# cs4272_test.net
KiCad netlist of a schematic drawn in EAGLE
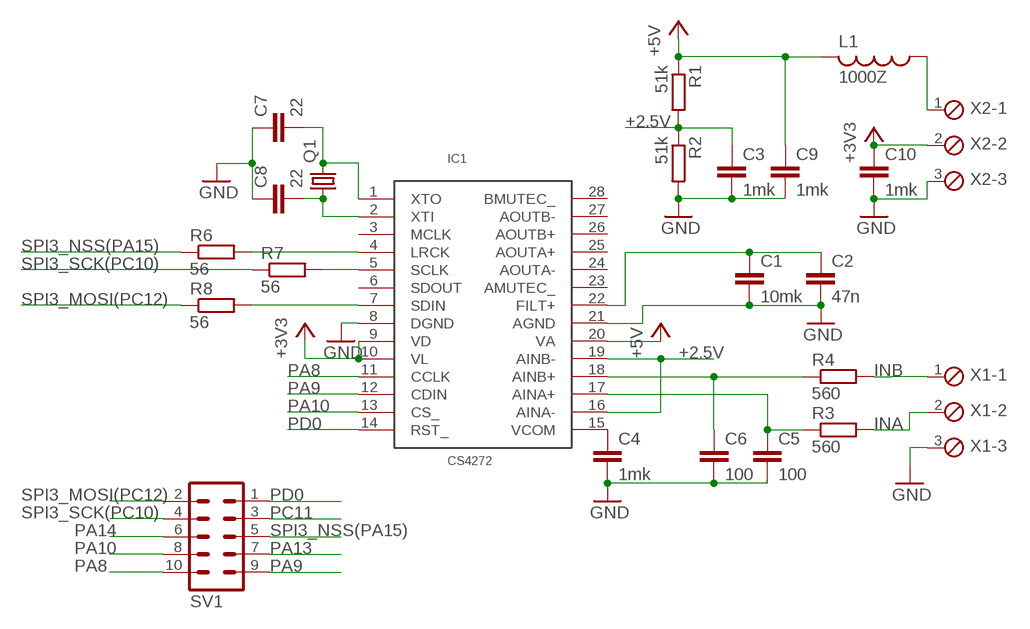
[diagram p0: schematic, sheet 1]

(export (version "E")
  (design (tool "Eeschema 10.0.6"))
  (components
    (comp (ref "C1")
      (value "10mk")
      (footprint "eagle-import:C0805")
      (libsource (lib "eagle-import") (part "C-EUC0805"))
    )
    (comp (ref "C2")
      (value "47n")
      (footprint "eagle-import:C0805")
      (libsource (lib "eagle-import") (part "C-EUC0805"))
    )
    (comp (ref "C3")
      (value "1mk")
      (footprint "eagle-import:C0603")
      (libsource (lib "eagle-import") (part "C-EUC0603"))
    )
    (comp (ref "C4")
      (value "1mk")
      (footprint "eagle-import:C0603")
      (libsource (lib "eagle-import") (part "C-EUC0603"))
    )
    (comp (ref "C5")
      (value "100")
      (footprint "eagle-import:C0805")
      (libsource (lib "eagle-import") (part "C-EUC0805"))
    )
    (comp (ref "C6")
      (value "100")
      (footprint "eagle-import:C0805")
      (libsource (lib "eagle-import") (part "C-EUC0805"))
    )
    (comp (ref "C7")
      (value "22")
      (footprint "eagle-import:C0603")
      (libsource (lib "eagle-import") (part "C-EUC0603"))
    )
    (comp (ref "C8")
      (value "22")
      (footprint "eagle-import:C0603")
      (libsource (lib "eagle-import") (part "C-EUC0603"))
    )
    (comp (ref "C9")
      (value "1mk")
      (footprint "eagle-import:C0603")
      (libsource (lib "eagle-import") (part "C-EUC0603"))
    )
    (comp (ref "C10")
      (value "1mk")
      (footprint "eagle-import:C0603")
      (libsource (lib "eagle-import") (part "C-EUC0603"))
    )
    (comp (ref "IC1")
      (value "CS4272")
      (footprint "eagle-import:TSSOP28")
      (libsource (lib "eagle-import") (part "CS4272"))
    )
    (comp (ref "L1")
      (value "1000Z")
      (footprint "eagle-import:C0805")
      (libsource (lib "eagle-import") (part "L-USL0805"))
    )
    (comp (ref "Q1")
      (value "CRYSTALHC49S")
      (footprint "eagle-import:HC49_S")
      (libsource (lib "eagle-import") (part "CRYSTALHC49S"))
    )
    (comp (ref "R1")
      (value "51k")
      (footprint "eagle-import:R0603")
      (libsource (lib "eagle-import") (part "R-EU_R0603"))
    )
    (comp (ref "R2")
      (value "51k")
      (footprint "eagle-import:R0603")
      (libsource (lib "eagle-import") (part "R-EU_R0603"))
    )
    (comp (ref "R3")
      (value "560")
      (footprint "eagle-import:R0603")
      (libsource (lib "eagle-import") (part "R-EU_R0603"))
    )
    (comp (ref "R4")
      (value "560")
      (footprint "eagle-import:R0603")
      (libsource (lib "eagle-import") (part "R-EU_R0603"))
    )
    (comp (ref "R6")
      (value "56")
      (footprint "eagle-import:R0603")
      (libsource (lib "eagle-import") (part "R-EU_R0603"))
    )
    (comp (ref "R7")
      (value "56")
      (footprint "eagle-import:R0603")
      (libsource (lib "eagle-import") (part "R-EU_R0603"))
    )
    (comp (ref "R8")
      (value "56")
      (footprint "eagle-import:R0603")
      (libsource (lib "eagle-import") (part "R-EU_R0603"))
    )
    (comp (ref "SV1")
      (value "ML10")
      (footprint "eagle-import:ML10")
      (libsource (lib "eagle-import") (part "ML10"))
    )
    (comp (ref "X1")
      (value "MPT3")
      (footprint "eagle-import:3POL254")
      (libsource (lib "eagle-import") (part "MPT3"))
    )
    (comp (ref "X2")
      (value "MPT3")
      (footprint "eagle-import:3POL254")
      (libsource (lib "eagle-import") (part "MPT3"))
    )
  )
  (nets
    (net (code "1") (name "+3V3") (class "Default")
      (node (ref "C10") (pin "1") (pinfunction "1_1") (pintype "passive"))
      (node (ref "IC1") (pin "10") (pinfunction "VL_10") (pintype "bidirectional"))
      (node (ref "IC1") (pin "9") (pinfunction "VD_9") (pintype "bidirectional"))
      (node (ref "X2") (pin "2") (pinfunction "1_2") (pintype "passive"))
    )
    (net (code "2") (name "+5V") (class "Default")
      (node (ref "C9") (pin "1") (pinfunction "1_1") (pintype "passive"))
      (node (ref "IC1") (pin "20") (pinfunction "VA_20") (pintype "bidirectional"))
      (node (ref "L1") (pin "2") (pinfunction "2_2") (pintype "passive"))
      (node (ref "R1") (pin "1") (pinfunction "1_1") (pintype "passive"))
    )
    (net (code "3") (name "/+2.5V") (class "Default")
      (node (ref "C3") (pin "1") (pinfunction "1_1") (pintype "passive"))
      (node (ref "IC1") (pin "16") (pinfunction "AINA-_16") (pintype "bidirectional"))
      (node (ref "IC1") (pin "19") (pinfunction "AINB-_19") (pintype "bidirectional"))
      (node (ref "R1") (pin "2") (pinfunction "2_2") (pintype "passive"))
      (node (ref "R2") (pin "1") (pinfunction "1_1") (pintype "passive"))
    )
    (net (code "4") (name "/INA") (class "Default")
      (node (ref "R3") (pin "2") (pinfunction "2_2") (pintype "passive"))
      (node (ref "X1") (pin "2") (pinfunction "1_2") (pintype "passive"))
    )
    (net (code "5") (name "/INB") (class "Default")
      (node (ref "R4") (pin "2") (pinfunction "2_2") (pintype "passive"))
      (node (ref "X1") (pin "1") (pinfunction "1_1") (pintype "passive"))
    )
    (net (code "6") (name "/PA8") (class "Default")
      (node (ref "IC1") (pin "11") (pinfunction "CCLK_11") (pintype "bidirectional"))
      (node (ref "SV1") (pin "10") (pinfunction "10_10") (pintype "passive"))
    )
    (net (code "7") (name "/PA9") (class "Default")
      (node (ref "IC1") (pin "12") (pinfunction "CDIN_12") (pintype "bidirectional"))
      (node (ref "SV1") (pin "9") (pinfunction "9_9") (pintype "passive"))
    )
    (net (code "8") (name "/PA10") (class "Default")
      (node (ref "IC1") (pin "13") (pinfunction "CS__13") (pintype "bidirectional"))
      (node (ref "SV1") (pin "8") (pinfunction "8_8") (pintype "passive"))
    )
    (net (code "9") (name "/PA13") (class "Default")
      (node (ref "SV1") (pin "7") (pinfunction "7_7") (pintype "passive"))
    )
    (net (code "10") (name "/PA14") (class "Default")
      (node (ref "SV1") (pin "6") (pinfunction "6_6") (pintype "passive"))
    )
    (net (code "11") (name "/PC11") (class "Default")
      (node (ref "SV1") (pin "3") (pinfunction "3_3") (pintype "passive"))
    )
    (net (code "12") (name "/PD0") (class "Default")
      (node (ref "IC1") (pin "14") (pinfunction "RST__14") (pintype "bidirectional"))
      (node (ref "SV1") (pin "1") (pinfunction "1_1") (pintype "passive"))
    )
    (net (code "13") (name "/SPI3_MOSI(PC12)") (class "Default")
      (node (ref "R8") (pin "1") (pinfunction "1_1") (pintype "passive"))
      (node (ref "SV1") (pin "2") (pinfunction "2_2") (pintype "passive"))
    )
    (net (code "14") (name "/SPI3_NSS(PA15)") (class "Default")
      (node (ref "R6") (pin "1") (pinfunction "1_1") (pintype "passive"))
      (node (ref "SV1") (pin "5") (pinfunction "5_5") (pintype "passive"))
    )
    (net (code "15") (name "/SPI3_SCK(PC10)") (class "Default")
      (node (ref "R7") (pin "1") (pinfunction "1_1") (pintype "passive"))
      (node (ref "SV1") (pin "4") (pinfunction "4_4") (pintype "passive"))
    )
    (net (code "16") (name "GND") (class "Default")
      (node (ref "C1") (pin "2") (pinfunction "2_2") (pintype "passive"))
      (node (ref "C10") (pin "2") (pinfunction "2_2") (pintype "passive"))
      (node (ref "C2") (pin "2") (pinfunction "2_2") (pintype "passive"))
      (node (ref "C3") (pin "2") (pinfunction "2_2") (pintype "passive"))
      (node (ref "C4") (pin "2") (pinfunction "2_2") (pintype "passive"))
      (node (ref "C5") (pin "2") (pinfunction "2_2") (pintype "passive"))
      (node (ref "C6") (pin "2") (pinfunction "2_2") (pintype "passive"))
      (node (ref "C7") (pin "1") (pinfunction "1_1") (pintype "passive"))
      (node (ref "C8") (pin "1") (pinfunction "1_1") (pintype "passive"))
      (node (ref "C9") (pin "2") (pinfunction "2_2") (pintype "passive"))
      (node (ref "IC1") (pin "21") (pinfunction "AGND_21") (pintype "bidirectional"))
      (node (ref "IC1") (pin "8") (pinfunction "DGND_8") (pintype "bidirectional"))
      (node (ref "R2") (pin "2") (pinfunction "2_2") (pintype "passive"))
      (node (ref "X1") (pin "3") (pinfunction "1_3") (pintype "passive"))
      (node (ref "X2") (pin "3") (pinfunction "1_3") (pintype "passive"))
    )
    (net (code "17") (name "Net-(IC1-AINA+)") (class "Default")
      (node (ref "C5") (pin "1") (pinfunction "1_1") (pintype "passive"))
      (node (ref "IC1") (pin "17") (pinfunction "AINA+_17") (pintype "bidirectional"))
      (node (ref "R3") (pin "1") (pinfunction "1_1") (pintype "passive"))
    )
    (net (code "18") (name "Net-(IC1-AINB+)") (class "Default")
      (node (ref "C6") (pin "1") (pinfunction "1_1") (pintype "passive"))
      (node (ref "IC1") (pin "18") (pinfunction "AINB+_18") (pintype "bidirectional"))
      (node (ref "R4") (pin "1") (pinfunction "1_1") (pintype "passive"))
    )
    (net (code "19") (name "Net-(IC1-FILT+)") (class "Default")
      (node (ref "C1") (pin "1") (pinfunction "1_1") (pintype "passive"))
      (node (ref "C2") (pin "1") (pinfunction "1_1") (pintype "passive"))
      (node (ref "IC1") (pin "22") (pinfunction "FILT+_22") (pintype "bidirectional"))
    )
    (net (code "20") (name "Net-(IC1-LRCK)") (class "Default")
      (node (ref "IC1") (pin "4") (pinfunction "LRCK_4") (pintype "bidirectional"))
      (node (ref "R6") (pin "2") (pinfunction "2_2") (pintype "passive"))
    )
    (net (code "21") (name "Net-(IC1-SCLK)") (class "Default")
      (node (ref "IC1") (pin "5") (pinfunction "SCLK_5") (pintype "bidirectional"))
      (node (ref "R7") (pin "2") (pinfunction "2_2") (pintype "passive"))
    )
    (net (code "22") (name "Net-(IC1-SDIN)") (class "Default")
      (node (ref "IC1") (pin "7") (pinfunction "SDIN_7") (pintype "bidirectional"))
      (node (ref "R8") (pin "2") (pinfunction "2_2") (pintype "passive"))
    )
    (net (code "23") (name "Net-(IC1-VCOM)") (class "Default")
      (node (ref "C4") (pin "1") (pinfunction "1_1") (pintype "passive"))
      (node (ref "IC1") (pin "15") (pinfunction "VCOM_15") (pintype "bidirectional"))
    )
    (net (code "24") (name "Net-(IC1-XTI)") (class "Default")
      (node (ref "C8") (pin "2") (pinfunction "2_2") (pintype "passive"))
      (node (ref "IC1") (pin "2") (pinfunction "XTI_2") (pintype "bidirectional"))
      (node (ref "Q1") (pin "1") (pinfunction "1_1") (pintype "passive"))
    )
    (net (code "25") (name "Net-(IC1-XTO)") (class "Default")
      (node (ref "C7") (pin "2") (pinfunction "2_2") (pintype "passive"))
      (node (ref "IC1") (pin "1") (pinfunction "XTO_1") (pintype "bidirectional"))
      (node (ref "Q1") (pin "2") (pinfunction "2_2") (pintype "passive"))
    )
    (net (code "26") (name "Net-(L1-Pad1)") (class "Default")
      (node (ref "L1") (pin "1") (pinfunction "1_1") (pintype "passive"))
      (node (ref "X2") (pin "1") (pinfunction "1_1") (pintype "passive"))
    )
    (net (code "27") (name "unconnected-(IC1-AMUTEC_-Pad23)") (class "Default")
      (node (ref "IC1") (pin "23") (pinfunction "AMUTEC__23") (pintype "bidirectional"))
    )
    (net (code "28") (name "unconnected-(IC1-AOUTA+-Pad25)") (class "Default")
      (node (ref "IC1") (pin "25") (pinfunction "AOUTA+_25") (pintype "bidirectional"))
    )
    (net (code "29") (name "unconnected-(IC1-AOUTA--Pad24)") (class "Default")
      (node (ref "IC1") (pin "24") (pinfunction "AOUTA-_24") (pintype "bidirectional"))
    )
    (net (code "30") (name "unconnected-(IC1-AOUTB+-Pad26)") (class "Default")
      (node (ref "IC1") (pin "26") (pinfunction "AOUTB+_26") (pintype "bidirectional"))
    )
    (net (code "31") (name "unconnected-(IC1-AOUTB--Pad27)") (class "Default")
      (node (ref "IC1") (pin "27") (pinfunction "AOUTB-_27") (pintype "bidirectional"))
    )
    (net (code "32") (name "unconnected-(IC1-BMUTEC_-Pad28)") (class "Default")
      (node (ref "IC1") (pin "28") (pinfunction "BMUTEC__28") (pintype "bidirectional"))
    )
    (net (code "33") (name "unconnected-(IC1-MCLK-Pad3)") (class "Default")
      (node (ref "IC1") (pin "3") (pinfunction "MCLK_3") (pintype "bidirectional"))
    )
    (net (code "34") (name "unconnected-(IC1-SDOUT-Pad6)") (class "Default")
      (node (ref "IC1") (pin "6") (pinfunction "SDOUT_6") (pintype "bidirectional"))
    )
  )
)
